# Completo.net
KiCad netlist of a schematic drawn in Altium Designer
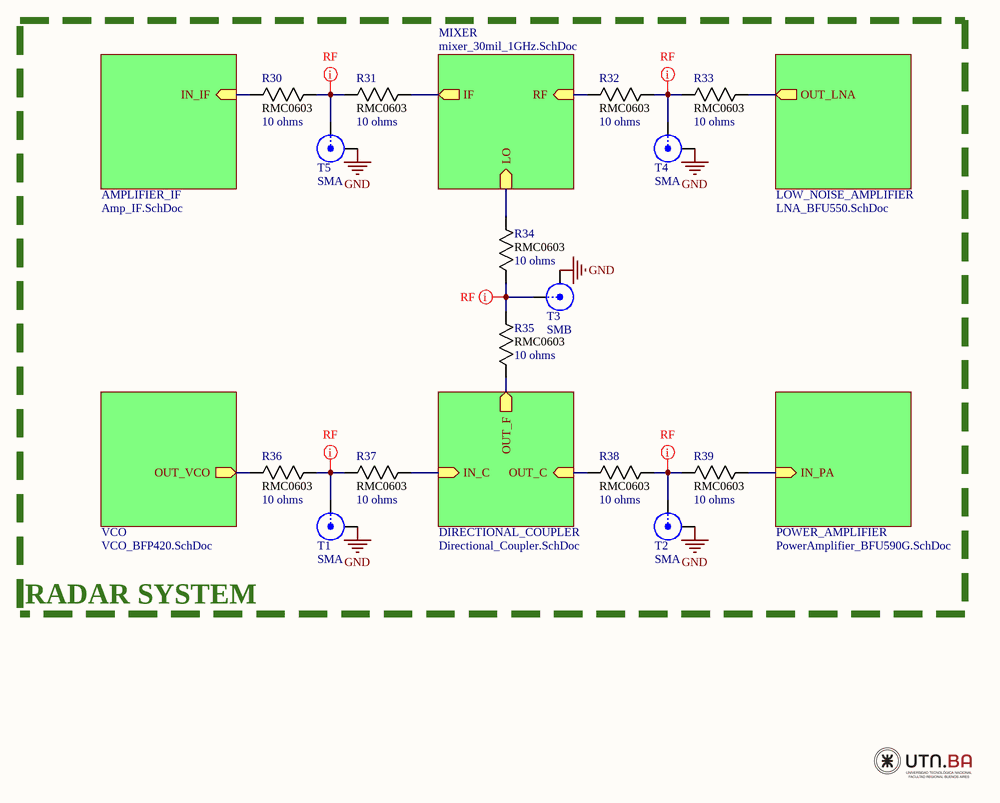
[diagram p0: Completo.SchDoc]

(export (version "E")
  (design (tool "Eeschema 10.0.6"))
  (components
    (comp (ref "R30")
      (value "10 ohms")
      (footprint "RMC0603")
      (description "Resistor RMC0603")
      (fields (field (name "Comment") "Resistor"))
      (libsource (lib "Radar_RF_EAIII") (part "Resistor"))
    )
    (comp (ref "R31")
      (value "10 ohms")
      (footprint "RMC0603")
      (description "Resistor RMC0603")
      (fields (field (name "Comment") "Resistor"))
      (libsource (lib "Radar_RF_EAIII") (part "Resistor"))
    )
    (comp (ref "R32")
      (value "10 ohms")
      (footprint "RMC0603")
      (description "Resistor RMC0603")
      (fields (field (name "Comment") "Resistor"))
      (libsource (lib "Radar_RF_EAIII") (part "Resistor"))
    )
    (comp (ref "R33")
      (value "10 ohms")
      (footprint "RMC0603")
      (description "Resistor RMC0603")
      (fields (field (name "Comment") "Resistor"))
      (libsource (lib "Radar_RF_EAIII") (part "Resistor"))
    )
    (comp (ref "R34")
      (value "10 ohms")
      (footprint "RMC0603")
      (description "Resistor RMC0603")
      (fields (field (name "Comment") "Resistor"))
      (libsource (lib "Radar_RF_EAIII") (part "Resistor"))
    )
    (comp (ref "R35")
      (value "10 ohms")
      (footprint "RMC0603")
      (description "Resistor RMC0603")
      (fields (field (name "Comment") "Resistor"))
      (libsource (lib "Radar_RF_EAIII") (part "Resistor"))
    )
    (comp (ref "R36")
      (value "10 ohms")
      (footprint "RMC0603")
      (description "Resistor RMC0603")
      (fields (field (name "Comment") "Resistor"))
      (libsource (lib "Radar_RF_EAIII") (part "Resistor"))
    )
    (comp (ref "R37")
      (value "10 ohms")
      (footprint "RMC0603")
      (description "Resistor RMC0603")
      (fields (field (name "Comment") "Resistor"))
      (libsource (lib "Radar_RF_EAIII") (part "Resistor"))
    )
    (comp (ref "R38")
      (value "10 ohms")
      (footprint "RMC0603")
      (description "Resistor RMC0603")
      (fields (field (name "Comment") "Resistor"))
      (libsource (lib "Radar_RF_EAIII") (part "Resistor"))
    )
    (comp (ref "R39")
      (value "10 ohms")
      (footprint "RMC0603")
      (description "Resistor RMC0603")
      (fields (field (name "Comment") "Resistor"))
      (libsource (lib "Radar_RF_EAIII") (part "Resistor"))
    )
    (comp (ref "T1")
      (value "SMA")
      (footprint "SMA-142-0701-851")
      (description "SMB Straight Connector")
      (fields (field (name "PUBLISHER") "Altium Limited"))
      (libsource (lib "PCB_Project") (part "SMB"))
    )
    (comp (ref "T2")
      (value "SMA")
      (footprint "SMA-142-0701-851")
      (description "SMB Straight Connector")
      (fields (field (name "PUBLISHER") "Altium Limited"))
      (libsource (lib "PCB_Project") (part "SMB"))
    )
    (comp (ref "T3")
      (value "SMB")
      (footprint "SMB_V-RJ45")
      (description "SMB Straight Connector")
      (fields (field (name "PUBLISHER") "Altium Limited"))
      (libsource (lib "Radar_RF_EAIII") (part "SMB"))
    )
    (comp (ref "T4")
      (value "SMA")
      (footprint "SMA-142-0701-851")
      (description "SMB Straight Connector")
      (fields (field (name "PUBLISHER") "Altium Limited"))
      (libsource (lib "PCB_Project") (part "SMB"))
    )
    (comp (ref "T5")
      (value "SMA")
      (footprint "SMA-142-0701-851")
      (description "SMB Straight Connector")
      (fields (field (name "PUBLISHER") "Altium Limited"))
      (libsource (lib "PCB_Project") (part "SMB"))
    )
  )
  (nets
    (net (code "1") (name "/IF") (class "Default")
      (node (ref "R31") (pin "2") (pinfunction "2_2") (pintype "passive"))
    )
    (net (code "2") (name "/IN_C") (class "Default")
      (node (ref "R37") (pin "2") (pinfunction "2_2") (pintype "passive"))
    )
    (net (code "3") (name "/IN_IF") (class "Default")
      (node (ref "R30") (pin "1") (pinfunction "1_1") (pintype "passive"))
    )
    (net (code "4") (name "/IN_PA") (class "Default")
      (node (ref "R39") (pin "2") (pinfunction "2_2") (pintype "passive"))
    )
    (net (code "5") (name "/LO") (class "Default")
      (node (ref "R34") (pin "2") (pinfunction "2_2") (pintype "passive"))
    )
    (net (code "6") (name "/OUT_C") (class "Default")
      (node (ref "R38") (pin "1") (pinfunction "1_1") (pintype "passive"))
    )
    (net (code "7") (name "/OUT_F") (class "Default")
      (node (ref "R35") (pin "1") (pinfunction "1_1") (pintype "passive"))
    )
    (net (code "8") (name "/OUT_LNA") (class "Default")
      (node (ref "R33") (pin "2") (pinfunction "2_2") (pintype "passive"))
    )
    (net (code "9") (name "/OUT_VCO") (class "Default")
      (node (ref "R36") (pin "1") (pinfunction "1_1") (pintype "passive"))
    )
    (net (code "10") (name "/RF") (class "Default")
      (node (ref "R32") (pin "1") (pinfunction "1_1") (pintype "passive"))
    )
    (net (code "11") (name "GND") (class "Default")
      (node (ref "T1") (pin "2") (pinfunction "Y_2") (pintype "passive"))
      (node (ref "T2") (pin "2") (pinfunction "Y_2") (pintype "passive"))
      (node (ref "T3") (pin "2") (pinfunction "Y_2") (pintype "passive"))
      (node (ref "T4") (pin "2") (pinfunction "Y_2") (pintype "passive"))
      (node (ref "T5") (pin "2") (pinfunction "Y_2") (pintype "passive"))
    )
    (net (code "12") (name "Net-(T1-X)") (class "Default")
      (node (ref "R36") (pin "2") (pinfunction "2_2") (pintype "passive"))
      (node (ref "R37") (pin "1") (pinfunction "1_1") (pintype "passive"))
      (node (ref "T1") (pin "1") (pinfunction "X_1") (pintype "passive"))
    )
    (net (code "13") (name "Net-(T2-X)") (class "Default")
      (node (ref "R38") (pin "2") (pinfunction "2_2") (pintype "passive"))
      (node (ref "R39") (pin "1") (pinfunction "1_1") (pintype "passive"))
      (node (ref "T2") (pin "1") (pinfunction "X_1") (pintype "passive"))
    )
    (net (code "14") (name "Net-(T3-X)") (class "Default")
      (node (ref "R34") (pin "1") (pinfunction "1_1") (pintype "passive"))
      (node (ref "R35") (pin "2") (pinfunction "2_2") (pintype "passive"))
      (node (ref "T3") (pin "1") (pinfunction "X_1") (pintype "passive"))
    )
    (net (code "15") (name "Net-(T4-X)") (class "Default")
      (node (ref "R32") (pin "2") (pinfunction "2_2") (pintype "passive"))
      (node (ref "R33") (pin "1") (pinfunction "1_1") (pintype "passive"))
      (node (ref "T4") (pin "1") (pinfunction "X_1") (pintype "passive"))
    )
    (net (code "16") (name "Net-(T5-X)") (class "Default")
      (node (ref "R30") (pin "2") (pinfunction "2_2") (pintype "passive"))
      (node (ref "R31") (pin "1") (pinfunction "1_1") (pintype "passive"))
      (node (ref "T5") (pin "1") (pinfunction "X_1") (pintype "passive"))
    )
  )
)
